# MCU_Signals.net
KiCad netlist of a schematic drawn in Altium Designer
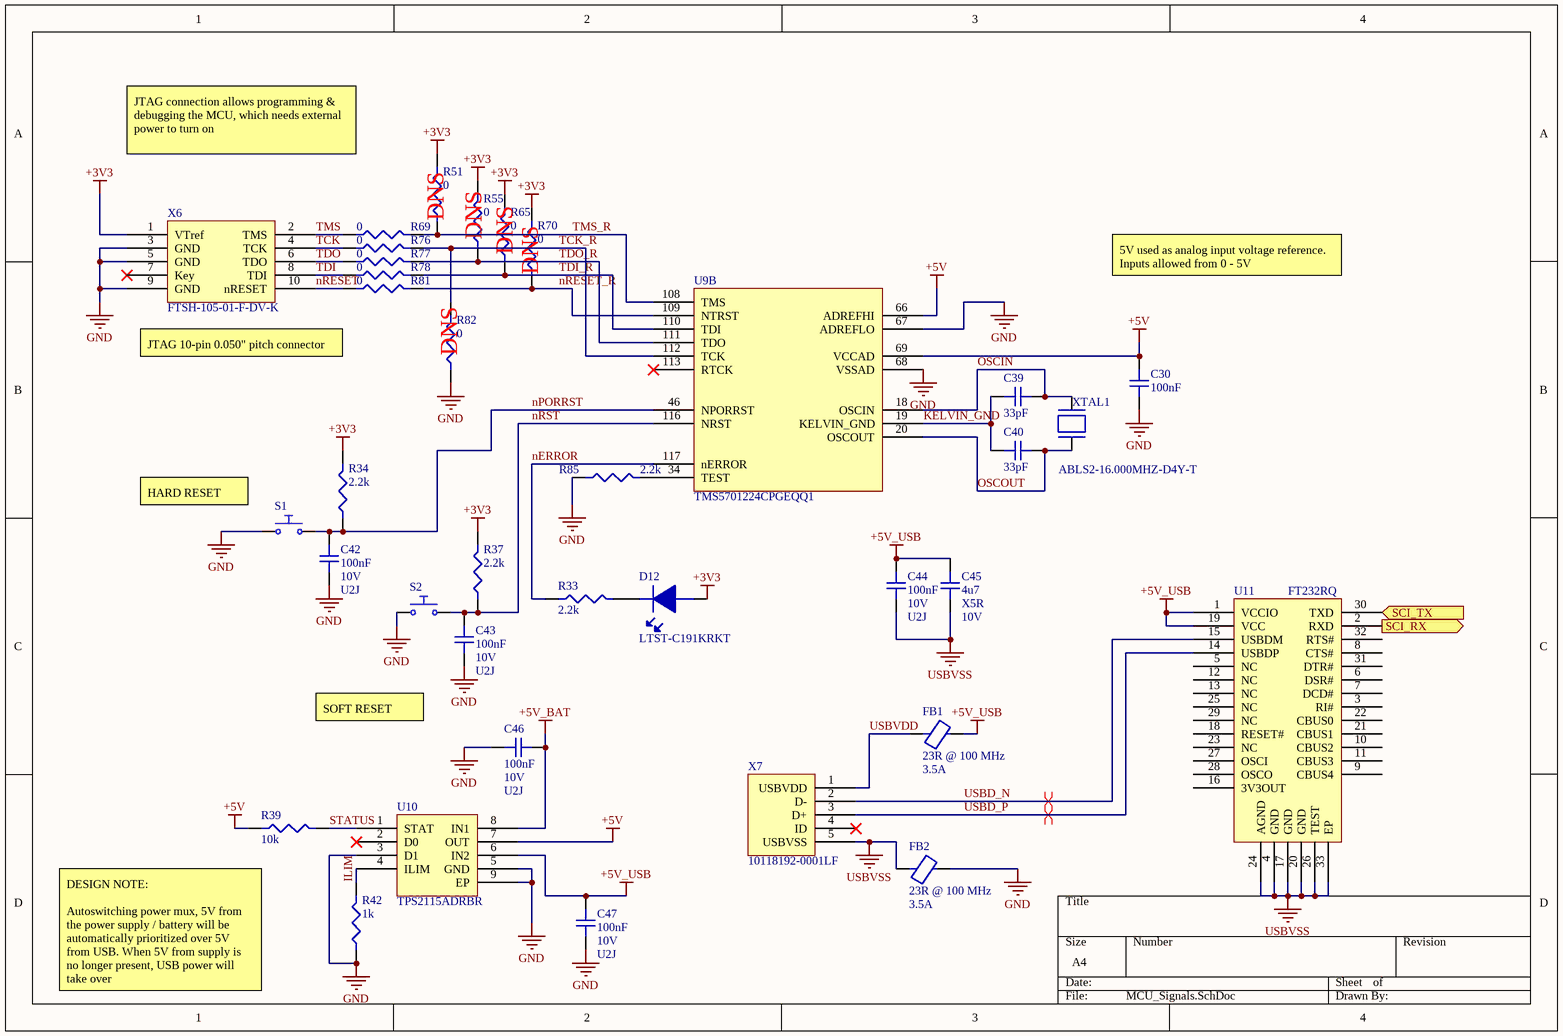
[diagram p0: MCU_Signals.SchDoc]

(export (version "E")
  (design (tool "Eeschema 10.0.6"))
  (components
    (comp (ref "C30")
      (value "100nF")
      (footprint "PHANTOM_FOOTPRINTS:C0805")
      (description "CAP MLCC 100nF 10Volts U2J 5%")
      (fields
        (field (name "MANUFACTURER") "Murata")
        (field (name "MANUFACTURER PART NUMBER") "GRM21B7U1A104JA01L")
      )
      (libsource (lib "PHANTOM_LIBRARY") (part "GRM21B7U1A104JA01L"))
    )
    (comp (ref "C39")
      (value "33pF")
      (footprint "C0805")
      (fields
        (field (name "MANUFACTURER") "Wurth Electronics")
        (field (name "MANUFACTURER PART NUMBER") "885012007003")
        (field (name "TOLERANCE") "5%")
      )
      (libsource (lib "PHANTOM_LIBRARY") (part "885012007003"))
    )
    (comp (ref "C40")
      (value "33pF")
      (footprint "C0805")
      (fields
        (field (name "MANUFACTURER") "Wurth Electronics")
        (field (name "MANUFACTURER PART NUMBER") "885012007003")
        (field (name "TOLERANCE") "5%")
      )
      (libsource (lib "PHANTOM_LIBRARY") (part "885012007003"))
    )
    (comp (ref "C42")
      (value "100nF")
      (footprint "PHANTOM_FOOTPRINTS:C0805")
      (description "CAP MLCC 100nF 10Volts U2J 5%")
      (fields
        (field (name "MANUFACTURER") "Murata")
        (field (name "MANUFACTURER PART NUMBER") "GRM21B7U1A104JA01L")
        (field (name "VOLTAGE RATING") "10V")
        (field (name "DIELECTRIC") "U2J")
      )
      (libsource (lib "PHANTOM_LIBRARY") (part "GRM21B7U1A104JA01L"))
    )
    (comp (ref "C43")
      (value "100nF")
      (footprint "PHANTOM_FOOTPRINTS:C0805")
      (description "CAP MLCC 100nF 10Volts U2J 5%")
      (fields
        (field (name "MANUFACTURER") "Murata")
        (field (name "MANUFACTURER PART NUMBER") "GRM21B7U1A104JA01L")
        (field (name "VOLTAGE RATING") "10V")
        (field (name "DIELECTRIC") "U2J")
      )
      (libsource (lib "PHANTOM_LIBRARY") (part "GRM21B7U1A104JA01L"))
    )
    (comp (ref "C44")
      (value "100nF")
      (footprint "PHANTOM_FOOTPRINTS:C0805")
      (description "CAP MLCC 100nF 10Volts U2J 5%")
      (fields
        (field (name "MANUFACTURER") "Murata")
        (field (name "MANUFACTURER PART NUMBER") "GRM21B7U1A104JA01L")
        (field (name "VOLTAGE RATING") "10V")
        (field (name "DIELECTRIC") "U2J")
      )
      (libsource (lib "PHANTOM_LIBRARY") (part "GRM21B7U1A104JA01L"))
    )
    (comp (ref "C45")
      (value "4u7")
      (footprint "C0805")
      (fields
        (field (name "MANUFACTURER") "Murata")
        (field (name "MANUFACTURER PART NUMBER") "GRM219R61A475KE34D")
        (field (name "TOLERANCE") "10%")
        (field (name "DIELECTRIC") "X5R")
        (field (name "VOLTAGE") "10V")
      )
      (libsource (lib "PHANTOM_LIBRARY") (part "GRM219R61A475KE34D"))
    )
    (comp (ref "C46")
      (value "100nF")
      (footprint "PHANTOM_FOOTPRINTS:C0805")
      (description "CAP MLCC 100nF 10Volts U2J 5%")
      (fields
        (field (name "MANUFACTURER") "Murata")
        (field (name "MANUFACTURER PART NUMBER") "GRM21B7U1A104JA01L")
        (field (name "VOLTAGE RATING") "10V")
        (field (name "DIELECTRIC") "U2J")
      )
      (libsource (lib "PHANTOM_LIBRARY") (part "GRM21B7U1A104JA01L"))
    )
    (comp (ref "C47")
      (value "100nF")
      (footprint "PHANTOM_FOOTPRINTS:C0805")
      (description "CAP MLCC 100nF 10Volts U2J 5%")
      (fields
        (field (name "MANUFACTURER") "Murata")
        (field (name "MANUFACTURER PART NUMBER") "GRM21B7U1A104JA01L")
        (field (name "VOLTAGE RATING") "10V")
        (field (name "DIELECTRIC") "U2J")
      )
      (libsource (lib "PHANTOM_LIBRARY") (part "GRM21B7U1A104JA01L"))
    )
    (comp (ref "D12")
      (value "LTST-C191KRKT")
      (footprint "LED_0603")
      (description "LED RED CLEAR 0603 SMD")
      (fields (field (name "MANUFACTURER") "Vishay Lite-On") (field (name "VOLTAGE") "2V"))
      (libsource (lib "PHANTOM_LIBRARY") (part "LTST-C191KRKT"))
    )
    (comp (ref "FB1")
      (value "23R @ 100 MHz")
      (footprint "FB_1806")
      (description "FERRITE BEAD Ind Chip Bead Multi-Layer 23Ohm 30% 100MHz Ferrite 3.5A 1806 T/R")
      (fields
        (field (name "MANUFACTURER") "Taiyo Yuden")
        (field (name "MANUFACTURER PART NUMBER") "FBMJ4516HL230NTV")
        (field (name "MAX CURRENT RATING") "3.5A")
      )
      (libsource (lib "PHANTOM_LIBRARY") (part "FBMJ4516HL230NTV"))
    )
    (comp (ref "FB2")
      (value "23R @ 100 MHz")
      (footprint "FB_1806")
      (description "FERRITE BEAD Ind Chip Bead Multi-Layer 23Ohm 30% 100MHz Ferrite 3.5A 1806 T/R")
      (fields
        (field (name "MANUFACTURER") "Taiyo Yuden")
        (field (name "MANUFACTURER PART NUMBER") "FBMJ4516HL230NTV")
        (field (name "MAX CURRENT RATING") "3.5A")
      )
      (libsource (lib "PHANTOM_LIBRARY") (part "FBMJ4516HL230NTV"))
    )
    (comp (ref "R33")
      (value "2.2k")
      (footprint "R0805")
      (description "RES SMD 2.2K OHM 5% 1/8W")
      (fields
        (field (name "MANUFACTURER") "Yageo")
        (field (name "MANUFACTURER PART NUMBER") "RC0805JR-072K2L")
      )
      (libsource (lib "PHANTOM_LIBRARY") (part "RC0805JR-072K2L"))
    )
    (comp (ref "R34")
      (value "2.2k")
      (footprint "R0805")
      (description "RES SMD 2.2K OHM 5% 1/8W")
      (fields
        (field (name "MANUFACTURER") "Yageo")
        (field (name "MANUFACTURER PART NUMBER") "RC0805JR-072K2L")
      )
      (libsource (lib "PHANTOM_LIBRARY") (part "RC0805JR-072K2L"))
    )
    (comp (ref "R37")
      (value "2.2k")
      (footprint "R0805")
      (description "RES SMD 2.2K OHM 5% 1/8W")
      (fields
        (field (name "MANUFACTURER") "Yageo")
        (field (name "MANUFACTURER PART NUMBER") "RC0805JR-072K2L")
      )
      (libsource (lib "PHANTOM_LIBRARY") (part "RC0805JR-072K2L"))
    )
    (comp (ref "R39")
      (value "10k")
      (footprint "R0805")
      (description "RES SMD 10K OHM 1% 1/8W 0805")
      (fields
        (field (name "MANUFACTURER") "Yageo Phycomp")
        (field (name "MANUFACTURER PART NUMBER") "RC0805FR-071KL")
      )
      (libsource (lib "PHANTOM_LIBRARY") (part "RC0805FR-071KL"))
    )
    (comp (ref "R42")
      (value "1k")
      (footprint "R0805")
      (description "RES SMD 1K OHM 0805 1K Ohm 0.1% 0.125W(1/8W) ±25ppm/C Molded SMD Automotive Punched T/R")
      (fields
        (field (name "MANUFACTURER") "Panasonic ECG")
        (field (name "MANUFACTURER PART NUMBER") "ERA-6AEB102V")
      )
      (libsource (lib "PHANTOM_LIBRARY") (part "ERA-6AEB102V"))
    )
    (comp (ref "R51")
      (value "0")
      (footprint "R0805")
      (description "RES SMD 0 OHM 1/8W 0805")
      (fields
        (field (name "MANUFACTURER") "Yageo")
        (field (name "MANUFACTURER PART NUMBER") "RC0805JR-070RL")
      )
      (libsource (lib "PHANTOM_LIBRARY") (part "RC0805JR-070RL"))
    )
    (comp (ref "R55")
      (value "0")
      (footprint "R0805")
      (description "RES SMD 0 OHM 1/8W 0805")
      (fields
        (field (name "MANUFACTURER") "Yageo")
        (field (name "MANUFACTURER PART NUMBER") "RC0805JR-070RL")
      )
      (libsource (lib "PHANTOM_LIBRARY") (part "RC0805JR-070RL"))
    )
    (comp (ref "R65")
      (value "0")
      (footprint "R0805")
      (description "RES SMD 0 OHM 1/8W 0805")
      (fields
        (field (name "MANUFACTURER") "Yageo")
        (field (name "MANUFACTURER PART NUMBER") "RC0805JR-070RL")
      )
      (libsource (lib "PHANTOM_LIBRARY") (part "RC0805JR-070RL"))
    )
    (comp (ref "R69")
      (value "0")
      (footprint "R0805")
      (description "RES SMD 0 OHM 1/8W 0805")
      (fields
        (field (name "MANUFACTURER") "Yageo")
        (field (name "MANUFACTURER PART NUMBER") "RC0805JR-070RL")
      )
      (libsource (lib "PHANTOM_LIBRARY") (part "RC0805JR-070RL"))
    )
    (comp (ref "R70")
      (value "0")
      (footprint "R0805")
      (description "RES SMD 0 OHM 1/8W 0805")
      (fields
        (field (name "MANUFACTURER") "Yageo")
        (field (name "MANUFACTURER PART NUMBER") "RC0805JR-070RL")
      )
      (libsource (lib "PHANTOM_LIBRARY") (part "RC0805JR-070RL"))
    )
    (comp (ref "R76")
      (value "0")
      (footprint "R0805")
      (description "RES SMD 0 OHM 1/8W 0805")
      (fields
        (field (name "MANUFACTURER") "Yageo")
        (field (name "MANUFACTURER PART NUMBER") "RC0805JR-070RL")
      )
      (libsource (lib "PHANTOM_LIBRARY") (part "RC0805JR-070RL"))
    )
    (comp (ref "R77")
      (value "0")
      (footprint "R0805")
      (description "RES SMD 0 OHM 1/8W 0805")
      (fields
        (field (name "MANUFACTURER") "Yageo")
        (field (name "MANUFACTURER PART NUMBER") "RC0805JR-070RL")
      )
      (libsource (lib "PHANTOM_LIBRARY") (part "RC0805JR-070RL"))
    )
    (comp (ref "R78")
      (value "0")
      (footprint "R0805")
      (description "RES SMD 0 OHM 1/8W 0805")
      (fields
        (field (name "MANUFACTURER") "Yageo")
        (field (name "MANUFACTURER PART NUMBER") "RC0805JR-070RL")
      )
      (libsource (lib "PHANTOM_LIBRARY") (part "RC0805JR-070RL"))
    )
    (comp (ref "R81")
      (value "0")
      (footprint "R0805")
      (description "RES SMD 0 OHM 1/8W 0805")
      (fields
        (field (name "MANUFACTURER") "Yageo")
        (field (name "MANUFACTURER PART NUMBER") "RC0805JR-070RL")
      )
      (libsource (lib "PHANTOM_LIBRARY") (part "RC0805JR-070RL"))
    )
    (comp (ref "R82")
      (value "0")
      (footprint "R0805")
      (description "RES SMD 0 OHM 1/8W 0805")
      (fields
        (field (name "MANUFACTURER") "Yageo")
        (field (name "MANUFACTURER PART NUMBER") "RC0805JR-070RL")
      )
      (libsource (lib "PHANTOM_LIBRARY") (part "RC0805JR-070RL"))
    )
    (comp (ref "R85")
      (value "2.2k")
      (footprint "R0805")
      (description "RES SMD 2.2K OHM 5% 1/8W")
      (fields
        (field (name "MANUFACTURER") "Yageo")
        (field (name "MANUFACTURER PART NUMBER") "RC0805JR-072K2L")
      )
      (libsource (lib "PHANTOM_LIBRARY") (part "RC0805JR-072K2L"))
    )
    (comp (ref "S1")
      (value "PTS645SM43SMTR92LFS")
      (footprint "PUSH_BUTTON")
      (description "SWITCH TACTILE SPST-NO 0.05A 12V")
      (fields (field (name "MANUFACTURER") "ITT C&K"))
      (libsource (lib "PHANTOM_LIBRARY") (part "PTS645SM43SMTR92LFS"))
    )
    (comp (ref "S2")
      (value "PTS645SM43SMTR92LFS")
      (footprint "PUSH_BUTTON")
      (description "SWITCH TACTILE SPST-NO 0.05A 12V")
      (fields (field (name "MANUFACTURER") "ITT C&K"))
      (libsource (lib "PHANTOM_LIBRARY") (part "PTS645SM43SMTR92LFS"))
    )
    (comp (ref "U9")
      (value "TMS5701224CPGEQQ1")
      (footprint "LQFP-144")
      (description "ARM CORTEX R4 LOCK STEP HERCULES MCU")
      (fields (field (name "MANUFACTURER") "Texas Instruments"))
      (libsource (lib "PHANTOM_LIBRARY") (part "TMS5701224CPGEQQ1"))
    )
    (comp (ref "U10")
      (value "TPS2115ADRBR")
      (footprint "VSON-8")
      (description "IC OR CTRLR SRC SELECT 8SON")
      (fields (field (name "MANUFACTURER") "Texas Instruments"))
      (libsource (lib "PHANTOM_LIBRARY") (part "TPS2115ADRBR"))
    )
    (comp (ref "U11")
      (value "FT232RQ")
      (footprint "QFN-32")
      (description "IC USB FS SERIAL UART 32-QFN")
      (fields (field (name "MANUFACTURER") "FTDI") (field (name "MANUFACTURER PART NUMBER") "FT232RQ-REEL"))
      (libsource (lib "PHANTOM_LIBRARY") (part "FT232RQ-REEL"))
    )
    (comp (ref "X6")
      (value "FTSH-105-01-F-DV-K")
      (footprint "JTAG_50mil_10pin")
      (description "CONN_JTAG_10pin .050 Connector Dual Header 10 Position Surface Mount")
      (fields (field (name "MANUFACTURER") "Samtec"))
      (libsource (lib "PHANTOM_LIBRARY") (part "FTSH-105-01-F-DV-K"))
    )
    (comp (ref "X7")
      (value "10118192-0001LF")
      (footprint "USB_MICRO")
      (description "CONN_USB - micro B USB 2.0 Receptacle Connector 5 Position Surface Mount, Right Angle, Horizontal")
      (fields (field (name "MANUFACTURER") "Amphenol FCI"))
      (libsource (lib "PHANTOM_LIBRARY") (part "10118192-0001LF"))
    )
    (comp (ref "XTAL1")
      (value "ABLS2-16.000MHZ-D4Y-T")
      (footprint "XTAL")
      (description "XTAL 16MHz ±30ppm Crystal 18pF 40 Ohm -40°C ~ 85°C  Surface Mount HC49/US")
      (fields (field (name "MANUFACTURER") "Abracon") (field (name "TOLERANCE") "30ppm"))
      (libsource (lib "PHANTOM_LIBRARY") (part "ABLS2-16.000MHZ-D4Y-T"))
    )
  )
  (nets
    (net (code "1") (name "+3V3") (class "Default")
      (node (ref "D12") (pin "1") (pinfunction "1_1") (pintype "passive"))
      (node (ref "R34") (pin "2") (pinfunction "2_2") (pintype "passive"))
      (node (ref "R37") (pin "2") (pinfunction "2_2") (pintype "passive"))
      (node (ref "R51") (pin "2") (pinfunction "2_2") (pintype "passive"))
      (node (ref "R55") (pin "2") (pinfunction "2_2") (pintype "passive"))
      (node (ref "R65") (pin "2") (pinfunction "2_2") (pintype "passive"))
      (node (ref "R70") (pin "2") (pinfunction "2_2") (pintype "passive"))
      (node (ref "X6") (pin "1") (pinfunction "VTref_1") (pintype "passive"))
    )
    (net (code "2") (name "+5V") (class "Default")
      (node (ref "C30") (pin "2") (pinfunction "2_2") (pintype "passive"))
      (node (ref "R39") (pin "1") (pinfunction "1_1") (pintype "passive"))
      (node (ref "U10") (pin "7") (pinfunction "OUT_7") (pintype "passive"))
      (node (ref "U9") (pin "66") (pinfunction "ADREFHI_66") (pintype "passive"))
      (node (ref "U9") (pin "69") (pinfunction "VCCAD_69") (pintype "passive"))
    )
    (net (code "3") (name "+5V_BAT") (class "Default")
      (node (ref "C46") (pin "2") (pinfunction "2_2") (pintype "passive"))
      (node (ref "U10") (pin "8") (pinfunction "IN1_8") (pintype "passive"))
    )
    (net (code "4") (name "+5V_USB") (class "Default")
      (node (ref "C44") (pin "2") (pinfunction "2_2") (pintype "passive"))
      (node (ref "C45") (pin "2") (pinfunction "2_2") (pintype "passive"))
      (node (ref "C47") (pin "1") (pinfunction "1_1") (pintype "passive"))
      (node (ref "FB1") (pin "2") (pinfunction "2_2") (pintype "passive"))
      (node (ref "U10") (pin "6") (pinfunction "IN2_6") (pintype "passive"))
      (node (ref "U11") (pin "1") (pinfunction "VCCIO_1") (pintype "passive"))
      (node (ref "U11") (pin "19") (pinfunction "VCC_19") (pintype "passive"))
    )
    (net (code "5") (name "/ILIM") (class "Default")
      (node (ref "R42") (pin "2") (pinfunction "2_2") (pintype "passive"))
      (node (ref "U10") (pin "4") (pinfunction "ILIM_4") (pintype "passive"))
    )
    (net (code "6") (name "/KELVIN_GND") (class "Default")
      (node (ref "C39") (pin "1") (pinfunction "1_1") (pintype "passive"))
      (node (ref "C40") (pin "1") (pinfunction "1_1") (pintype "passive"))
      (node (ref "U9") (pin "19") (pinfunction "KELVIN_GND_19") (pintype "passive"))
    )
    (net (code "7") (name "/OSCIN") (class "Default")
      (node (ref "C39") (pin "2") (pinfunction "2_2") (pintype "passive"))
      (node (ref "U9") (pin "18") (pinfunction "OSCIN_18") (pintype "passive"))
      (node (ref "XTAL1") (pin "1") (pintype "passive"))
    )
    (net (code "8") (name "/OSCOUT") (class "Default")
      (node (ref "C40") (pin "2") (pinfunction "2_2") (pintype "passive"))
      (node (ref "U9") (pin "20") (pinfunction "OSCOUT_20") (pintype "passive"))
      (node (ref "XTAL1") (pin "2") (pintype "passive"))
    )
    (net (code "9") (name "/SCI_RX") (class "Default")
      (node (ref "U11") (pin "2") (pinfunction "RXD_2") (pintype "passive"))
    )
    (net (code "10") (name "/SCI_TX") (class "Default")
      (node (ref "U11") (pin "30") (pinfunction "TXD_30") (pintype "passive"))
    )
    (net (code "11") (name "/STATUS") (class "Default")
      (node (ref "R39") (pin "2") (pinfunction "2_2") (pintype "passive"))
      (node (ref "U10") (pin "1") (pinfunction "STAT_1") (pintype "passive"))
    )
    (net (code "12") (name "/TCK") (class "Default")
      (node (ref "R76") (pin "1") (pinfunction "1_1") (pintype "passive"))
      (node (ref "X6") (pin "4") (pinfunction "TCK_4") (pintype "passive"))
    )
    (net (code "13") (name "/TCK_R") (class "Default")
      (node (ref "R76") (pin "2") (pinfunction "2_2") (pintype "passive"))
      (node (ref "R82") (pin "2") (pinfunction "2_2") (pintype "passive"))
      (node (ref "U9") (pin "112") (pinfunction "TCK_112") (pintype "passive"))
    )
    (net (code "14") (name "/TDI") (class "Default")
      (node (ref "R78") (pin "1") (pinfunction "1_1") (pintype "passive"))
      (node (ref "X6") (pin "8") (pinfunction "TDI_8") (pintype "passive"))
    )
    (net (code "15") (name "/TDI_R") (class "Default")
      (node (ref "R65") (pin "1") (pinfunction "1_1") (pintype "passive"))
      (node (ref "R78") (pin "2") (pinfunction "2_2") (pintype "passive"))
      (node (ref "U9") (pin "110") (pinfunction "TDI_110") (pintype "passive"))
    )
    (net (code "16") (name "/TDO") (class "Default")
      (node (ref "R77") (pin "1") (pinfunction "1_1") (pintype "passive"))
      (node (ref "X6") (pin "6") (pinfunction "TDO_6") (pintype "passive"))
    )
    (net (code "17") (name "/TDO_R") (class "Default")
      (node (ref "R55") (pin "1") (pinfunction "1_1") (pintype "passive"))
      (node (ref "R77") (pin "2") (pinfunction "2_2") (pintype "passive"))
      (node (ref "U9") (pin "111") (pinfunction "TDO_111") (pintype "passive"))
    )
    (net (code "18") (name "/TMS") (class "Default")
      (node (ref "R69") (pin "1") (pinfunction "1_1") (pintype "passive"))
      (node (ref "X6") (pin "2") (pinfunction "TMS_2") (pintype "passive"))
    )
    (net (code "19") (name "/TMS_R") (class "Default")
      (node (ref "R51") (pin "1") (pinfunction "1_1") (pintype "passive"))
      (node (ref "R69") (pin "2") (pinfunction "2_2") (pintype "passive"))
      (node (ref "U9") (pin "108") (pinfunction "TMS_108") (pintype "passive"))
    )
    (net (code "20") (name "/USBD_N") (class "Default")
      (node (ref "U11") (pin "15") (pinfunction "USBDM_15") (pintype "passive"))
      (node (ref "X7") (pin "2") (pinfunction "D-_2") (pintype "passive"))
    )
    (net (code "21") (name "/USBD_P") (class "Default")
      (node (ref "U11") (pin "14") (pinfunction "USBDP_14") (pintype "passive"))
      (node (ref "X7") (pin "3") (pinfunction "D+_3") (pintype "passive"))
    )
    (net (code "22") (name "/USBVDD") (class "Default")
      (node (ref "FB1") (pin "1") (pinfunction "1_1") (pintype "passive"))
      (node (ref "X7") (pin "1") (pinfunction "USBVDD_1") (pintype "passive"))
    )
    (net (code "23") (name "/nERROR") (class "Default")
      (node (ref "R33") (pin "1") (pinfunction "1_1") (pintype "passive"))
      (node (ref "U9") (pin "117") (pinfunction "nERROR_117") (pintype "passive"))
    )
    (net (code "24") (name "/nPORRST") (class "Default")
      (node (ref "C42") (pin "2") (pinfunction "2_2") (pintype "passive"))
      (node (ref "R34") (pin "1") (pinfunction "1_1") (pintype "passive"))
      (node (ref "S1") (pin "2") (pinfunction "2_2") (pintype "passive"))
      (node (ref "U9") (pin "46") (pinfunction "NPORRST_46") (pintype "passive"))
    )
    (net (code "25") (name "/nRESET") (class "Default")
      (node (ref "R81") (pin "1") (pinfunction "1_1") (pintype "passive"))
      (node (ref "X6") (pin "10") (pinfunction "nRESET_10") (pintype "passive"))
    )
    (net (code "26") (name "/nRESET_R") (class "Default")
      (node (ref "R70") (pin "1") (pinfunction "1_1") (pintype "passive"))
      (node (ref "R81") (pin "2") (pinfunction "2_2") (pintype "passive"))
      (node (ref "U9") (pin "109") (pinfunction "NTRST_109") (pintype "passive"))
    )
    (net (code "27") (name "/nRST") (class "Default")
      (node (ref "C43") (pin "2") (pinfunction "2_2") (pintype "passive"))
      (node (ref "R37") (pin "1") (pinfunction "1_1") (pintype "passive"))
      (node (ref "S2") (pin "2") (pinfunction "2_2") (pintype "passive"))
      (node (ref "U9") (pin "116") (pinfunction "NRST_116") (pintype "passive"))
    )
    (net (code "28") (name "GND") (class "Default")
      (node (ref "C30") (pin "1") (pinfunction "1_1") (pintype "passive"))
      (node (ref "C42") (pin "1") (pinfunction "1_1") (pintype "passive"))
      (node (ref "C43") (pin "1") (pinfunction "1_1") (pintype "passive"))
      (node (ref "C46") (pin "1") (pinfunction "1_1") (pintype "passive"))
      (node (ref "C47") (pin "2") (pinfunction "2_2") (pintype "passive"))
      (node (ref "FB2") (pin "2") (pinfunction "2_2") (pintype "passive"))
      (node (ref "R42") (pin "1") (pinfunction "1_1") (pintype "passive"))
      (node (ref "R82") (pin "1") (pinfunction "1_1") (pintype "passive"))
      (node (ref "R85") (pin "1") (pinfunction "1_1") (pintype "passive"))
      (node (ref "S1") (pin "1") (pinfunction "1_1") (pintype "passive"))
      (node (ref "S2") (pin "1") (pinfunction "1_1") (pintype "passive"))
      (node (ref "U10") (pin "3") (pinfunction "D1_3") (pintype "passive"))
      (node (ref "U10") (pin "5") (pinfunction "GND_5") (pintype "passive"))
      (node (ref "U10") (pin "9") (pinfunction "EP_9") (pintype "passive"))
      (node (ref "U9") (pin "67") (pinfunction "ADREFLO_67") (pintype "passive"))
      (node (ref "U9") (pin "68") (pinfunction "VSSAD_68") (pintype "passive"))
      (node (ref "X6") (pin "3") (pinfunction "GND_3") (pintype "passive"))
      (node (ref "X6") (pin "5") (pinfunction "GND_5") (pintype "passive"))
      (node (ref "X6") (pin "9") (pinfunction "GND_9") (pintype "passive"))
    )
    (net (code "29") (name "Net-(D12-Pad2)") (class "Default")
      (node (ref "D12") (pin "2") (pinfunction "2_2") (pintype "passive"))
      (node (ref "R33") (pin "2") (pinfunction "2_2") (pintype "passive"))
    )
    (net (code "30") (name "Net-(U9B-TEST)") (class "Default")
      (node (ref "R85") (pin "2") (pinfunction "2_2") (pintype "passive"))
      (node (ref "U9") (pin "34") (pinfunction "TEST_34") (pintype "passive"))
    )
    (net (code "31") (name "USBVSS") (class "Default")
      (node (ref "C44") (pin "1") (pinfunction "1_1") (pintype "passive"))
      (node (ref "C45") (pin "1") (pinfunction "1_1") (pintype "passive"))
      (node (ref "FB2") (pin "1") (pinfunction "1_1") (pintype "passive"))
      (node (ref "U11") (pin "17") (pinfunction "GND_17") (pintype "passive"))
      (node (ref "U11") (pin "20") (pinfunction "GND_20") (pintype "passive"))
      (node (ref "U11") (pin "24") (pinfunction "AGND_24") (pintype "passive"))
      (node (ref "U11") (pin "26") (pinfunction "TEST_26") (pintype "passive"))
      (node (ref "U11") (pin "33") (pinfunction "EP_33") (pintype "passive"))
      (node (ref "U11") (pin "4") (pinfunction "GND_4") (pintype "passive"))
      (node (ref "X7") (pin "5") (pinfunction "USBVSS_5") (pintype "passive"))
    )
    (net (code "32") (name "unconnected-(U9B-RTCK-Pad113)") (class "Default")
      (node (ref "U9") (pin "113") (pinfunction "RTCK_113") (pintype "passive+no_connect"))
    )
    (net (code "33") (name "unconnected-(U10-D0-Pad2)") (class "Default")
      (node (ref "U10") (pin "2") (pinfunction "D0_2") (pintype "passive+no_connect"))
    )
    (net (code "34") (name "unconnected-(U11-3V3OUT-Pad16)") (class "Default")
      (node (ref "U11") (pin "16") (pinfunction "3V3OUT_16") (pintype "passive"))
    )
    (net (code "35") (name "unconnected-(U11-CBUS0-Pad22)") (class "Default")
      (node (ref "U11") (pin "22") (pinfunction "CBUS0_22") (pintype "passive"))
    )
    (net (code "36") (name "unconnected-(U11-CBUS1-Pad21)") (class "Default")
      (node (ref "U11") (pin "21") (pinfunction "CBUS1_21") (pintype "passive"))
    )
    (net (code "37") (name "unconnected-(U11-CBUS2-Pad10)") (class "Default")
      (node (ref "U11") (pin "10") (pinfunction "CBUS2_10") (pintype "passive"))
    )
    (net (code "38") (name "unconnected-(U11-CBUS3-Pad11)") (class "Default")
      (node (ref "U11") (pin "11") (pinfunction "CBUS3_11") (pintype "passive"))
    )
    (net (code "39") (name "unconnected-(U11-CBUS4-Pad9)") (class "Default")
      (node (ref "U11") (pin "9") (pinfunction "CBUS4_9") (pintype "passive"))
    )
    (net (code "40") (name "unconnected-(U11-CTS#-Pad8)") (class "Default")
      (node (ref "U11") (pin "8") (pinfunction "CTS#_8") (pintype "passive"))
    )
    (net (code "41") (name "unconnected-(U11-DCD#-Pad7)") (class "Default")
      (node (ref "U11") (pin "7") (pinfunction "DCD#_7") (pintype "passive"))
    )
    (net (code "42") (name "unconnected-(U11-DSR#-Pad6)") (class "Default")
      (node (ref "U11") (pin "6") (pinfunction "DSR#_6") (pintype "passive"))
    )
    (net (code "43") (name "unconnected-(U11-DTR#-Pad31)") (class "Default")
      (node (ref "U11") (pin "31") (pinfunction "DTR#_31") (pintype "passive"))
    )
    (net (code "44") (name "unconnected-(U11-NC-Pad5)") (class "Default")
      (node (ref "U11") (pin "5") (pinfunction "NC_5") (pintype "passive"))
    )
    (net (code "45") (name "unconnected-(U11-NC-Pad12)") (class "Default")
      (node (ref "U11") (pin "12") (pinfunction "NC_12") (pintype "passive"))
    )
    (net (code "46") (name "unconnected-(U11-NC-Pad13)") (class "Default")
      (node (ref "U11") (pin "13") (pinfunction "NC_13") (pintype "passive"))
    )
    (net (code "47") (name "unconnected-(U11-NC-Pad23)") (class "Default")
      (node (ref "U11") (pin "23") (pinfunction "NC_23") (pintype "passive"))
    )
    (net (code "48") (name "unconnected-(U11-NC-Pad25)") (class "Default")
      (node (ref "U11") (pin "25") (pinfunction "NC_25") (pintype "passive"))
    )
    (net (code "49") (name "unconnected-(U11-NC-Pad29)") (class "Default")
      (node (ref "U11") (pin "29") (pinfunction "NC_29") (pintype "passive"))
    )
    (net (code "50") (name "unconnected-(U11-OSCI-Pad27)") (class "Default")
      (node (ref "U11") (pin "27") (pinfunction "OSCI_27") (pintype "passive"))
    )
    (net (code "51") (name "unconnected-(U11-OSCO-Pad28)") (class "Default")
      (node (ref "U11") (pin "28") (pinfunction "OSCO_28") (pintype "passive"))
    )
    (net (code "52") (name "unconnected-(U11-RESET#-Pad18)") (class "Default")
      (node (ref "U11") (pin "18") (pinfunction "RESET#_18") (pintype "passive"))
    )
    (net (code "53") (name "unconnected-(U11-RI#-Pad3)") (class "Default")
      (node (ref "U11") (pin "3") (pinfunction "RI#_3") (pintype "passive"))
    )
    (net (code "54") (name "unconnected-(U11-RTS#-Pad32)") (class "Default")
      (node (ref "U11") (pin "32") (pinfunction "RTS#_32") (pintype "passive"))
    )
    (net (code "55") (name "unconnected-(X6-Key-Pad7)") (class "Default")
      (node (ref "X6") (pin "7") (pinfunction "Key_7") (pintype "passive+no_connect"))
    )
    (net (code "56") (name "unconnected-(X7-ID-Pad4)") (class "Default")
      (node (ref "X7") (pin "4") (pinfunction "ID_4") (pintype "passive+no_connect"))
    )
  )
)
